# TCRT5000_-_MODULO.net
KiCad netlist of a schematic drawn in EAGLE
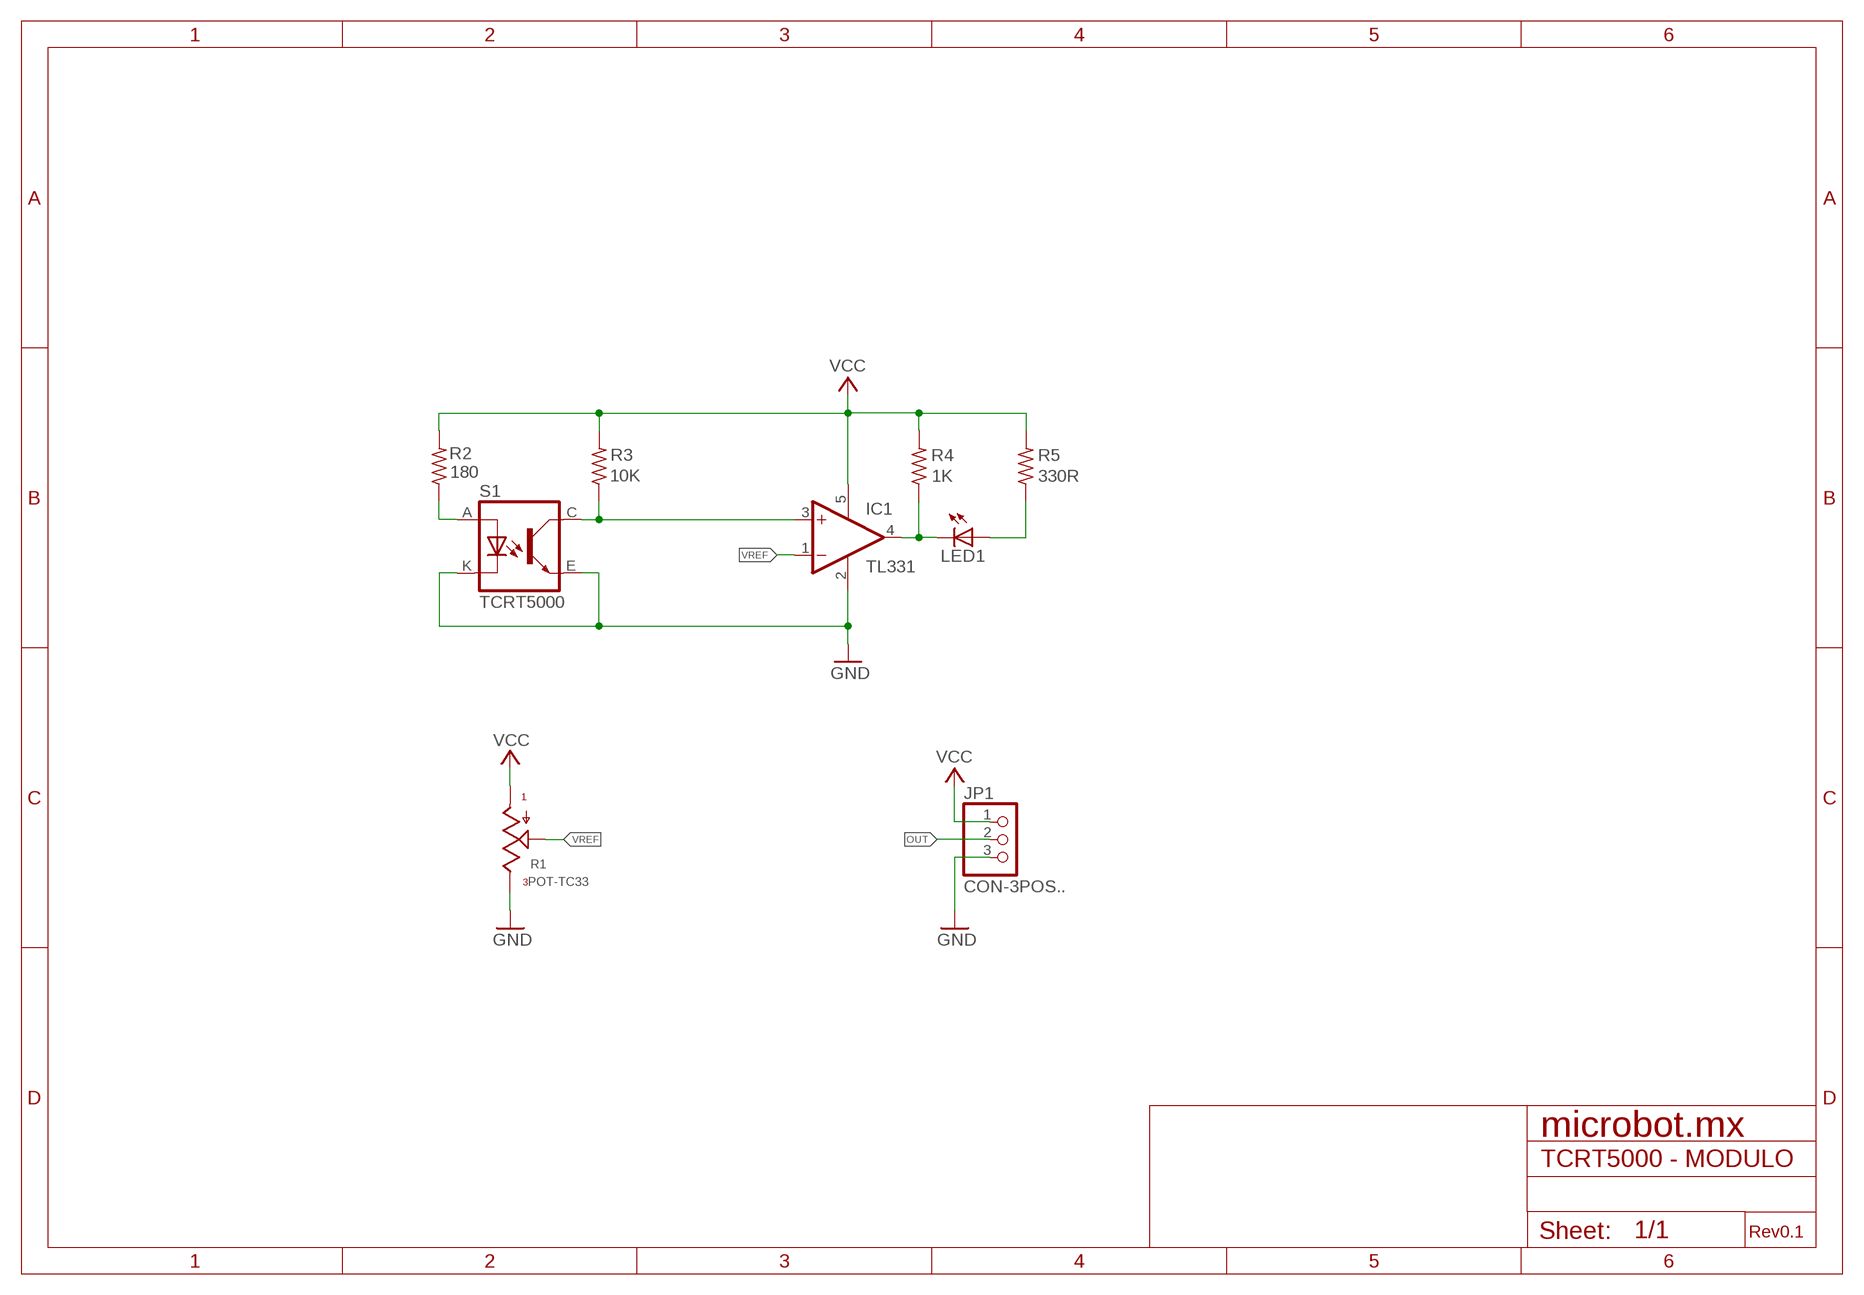
[diagram p0: schematic, sheet 1]

(export (version "E")
  (design (tool "Eeschema 10.0.6"))
  (components
    (comp (ref "IC1")
      (value "TL331")
      (footprint "eagle-import:DBV-R-PDSO-G5")
      (libsource (lib "eagle-import") (part "TL331"))
    )
    (comp (ref "JP1")
      (value "CON-3POS..")
      (footprint "eagle-import:1X03-GND")
      (libsource (lib "eagle-import") (part "CON-3POS.."))
    )
    (comp (ref "LED1")
      (value "LEDCHIPLED_1206")
      (footprint "eagle-import:CHIPLED_1206")
      (libsource (lib "eagle-import") (part "LEDCHIPLED_1206"))
    )
    (comp (ref "R1")
      (value "POT-TC33")
      (footprint "eagle-import:TC33")
      (libsource (lib "eagle-import") (part "POT-TC33"))
    )
    (comp (ref "R2")
      (value "180")
      (footprint "eagle-import:R1206")
      (libsource (lib "eagle-import") (part "R-US_R1206"))
    )
    (comp (ref "R3")
      (value "10K")
      (footprint "eagle-import:R1206")
      (libsource (lib "eagle-import") (part "R-US_R1206"))
    )
    (comp (ref "R4")
      (value "1K")
      (footprint "eagle-import:R1206")
      (libsource (lib "eagle-import") (part "R-US_R1206"))
    )
    (comp (ref "R5")
      (value "330R")
      (footprint "eagle-import:R1206")
      (libsource (lib "eagle-import") (part "R-US_R1206"))
    )
    (comp (ref "S1")
      (value "TCRT5000")
      (footprint "eagle-import:TCRT5000")
      (libsource (lib "eagle-import") (part "TCRT5000"))
    )
  )
  (nets
    (net (code "1") (name "GND") (class "Default")
      (node (ref "IC1") (pin "2") (pinfunction "GND_2") (pintype "power_in"))
      (node (ref "JP1") (pin "3") (pinfunction "3_3") (pintype "passive"))
      (node (ref "R1") (pin "3") (pinfunction "3_3") (pintype "passive"))
      (node (ref "S1") (pin "E") (pinfunction "EMISOR_E") (pintype "passive"))
      (node (ref "S1") (pin "K") (pinfunction "CÁTODO_K") (pintype "passive"))
    )
    (net (code "2") (name "Net-(IC1-+IN)") (class "Default")
      (node (ref "IC1") (pin "3") (pinfunction "+IN_3") (pintype "input"))
      (node (ref "R3") (pin "1") (pinfunction "1_1") (pintype "passive"))
      (node (ref "S1") (pin "C") (pinfunction "COLECTOR_C") (pintype "passive"))
    )
    (net (code "3") (name "Net-(LED1-PadA)") (class "Default")
      (node (ref "LED1") (pin "A") (pinfunction "A_A") (pintype "passive"))
      (node (ref "R5") (pin "1") (pinfunction "1_1") (pintype "passive"))
    )
    (net (code "4") (name "Net-(S1-ÁNODO)") (class "Default")
      (node (ref "R2") (pin "1") (pinfunction "1_1") (pintype "passive"))
      (node (ref "S1") (pin "A") (pinfunction "ÁNODO_A") (pintype "passive"))
    )
    (net (code "5") (name "OUT") (class "Default")
      (node (ref "IC1") (pin "4") (pinfunction "OUT_4") (pintype "output"))
      (node (ref "JP1") (pin "2") (pinfunction "2_2") (pintype "passive"))
      (node (ref "LED1") (pin "C") (pinfunction "C_C") (pintype "passive"))
      (node (ref "R4") (pin "1") (pinfunction "1_1") (pintype "passive"))
    )
    (net (code "6") (name "VCC") (class "Default")
      (node (ref "IC1") (pin "5") (pinfunction "V+_5") (pintype "power_in"))
      (node (ref "JP1") (pin "1") (pinfunction "1_1") (pintype "passive"))
      (node (ref "R1") (pin "1") (pinfunction "1_1") (pintype "passive"))
      (node (ref "R2") (pin "2") (pinfunction "2_2") (pintype "passive"))
      (node (ref "R3") (pin "2") (pinfunction "2_2") (pintype "passive"))
      (node (ref "R4") (pin "2") (pinfunction "2_2") (pintype "passive"))
      (node (ref "R5") (pin "2") (pinfunction "2_2") (pintype "passive"))
    )
    (net (code "7") (name "VREF") (class "Default")
      (node (ref "IC1") (pin "1") (pinfunction "-IN_1") (pintype "input"))
      (node (ref "R1") (pin "2") (pinfunction "2_2") (pintype "passive"))
    )
  )
)
